# XO345-1B.net
KiCad netlist of a schematic drawn in EAGLE
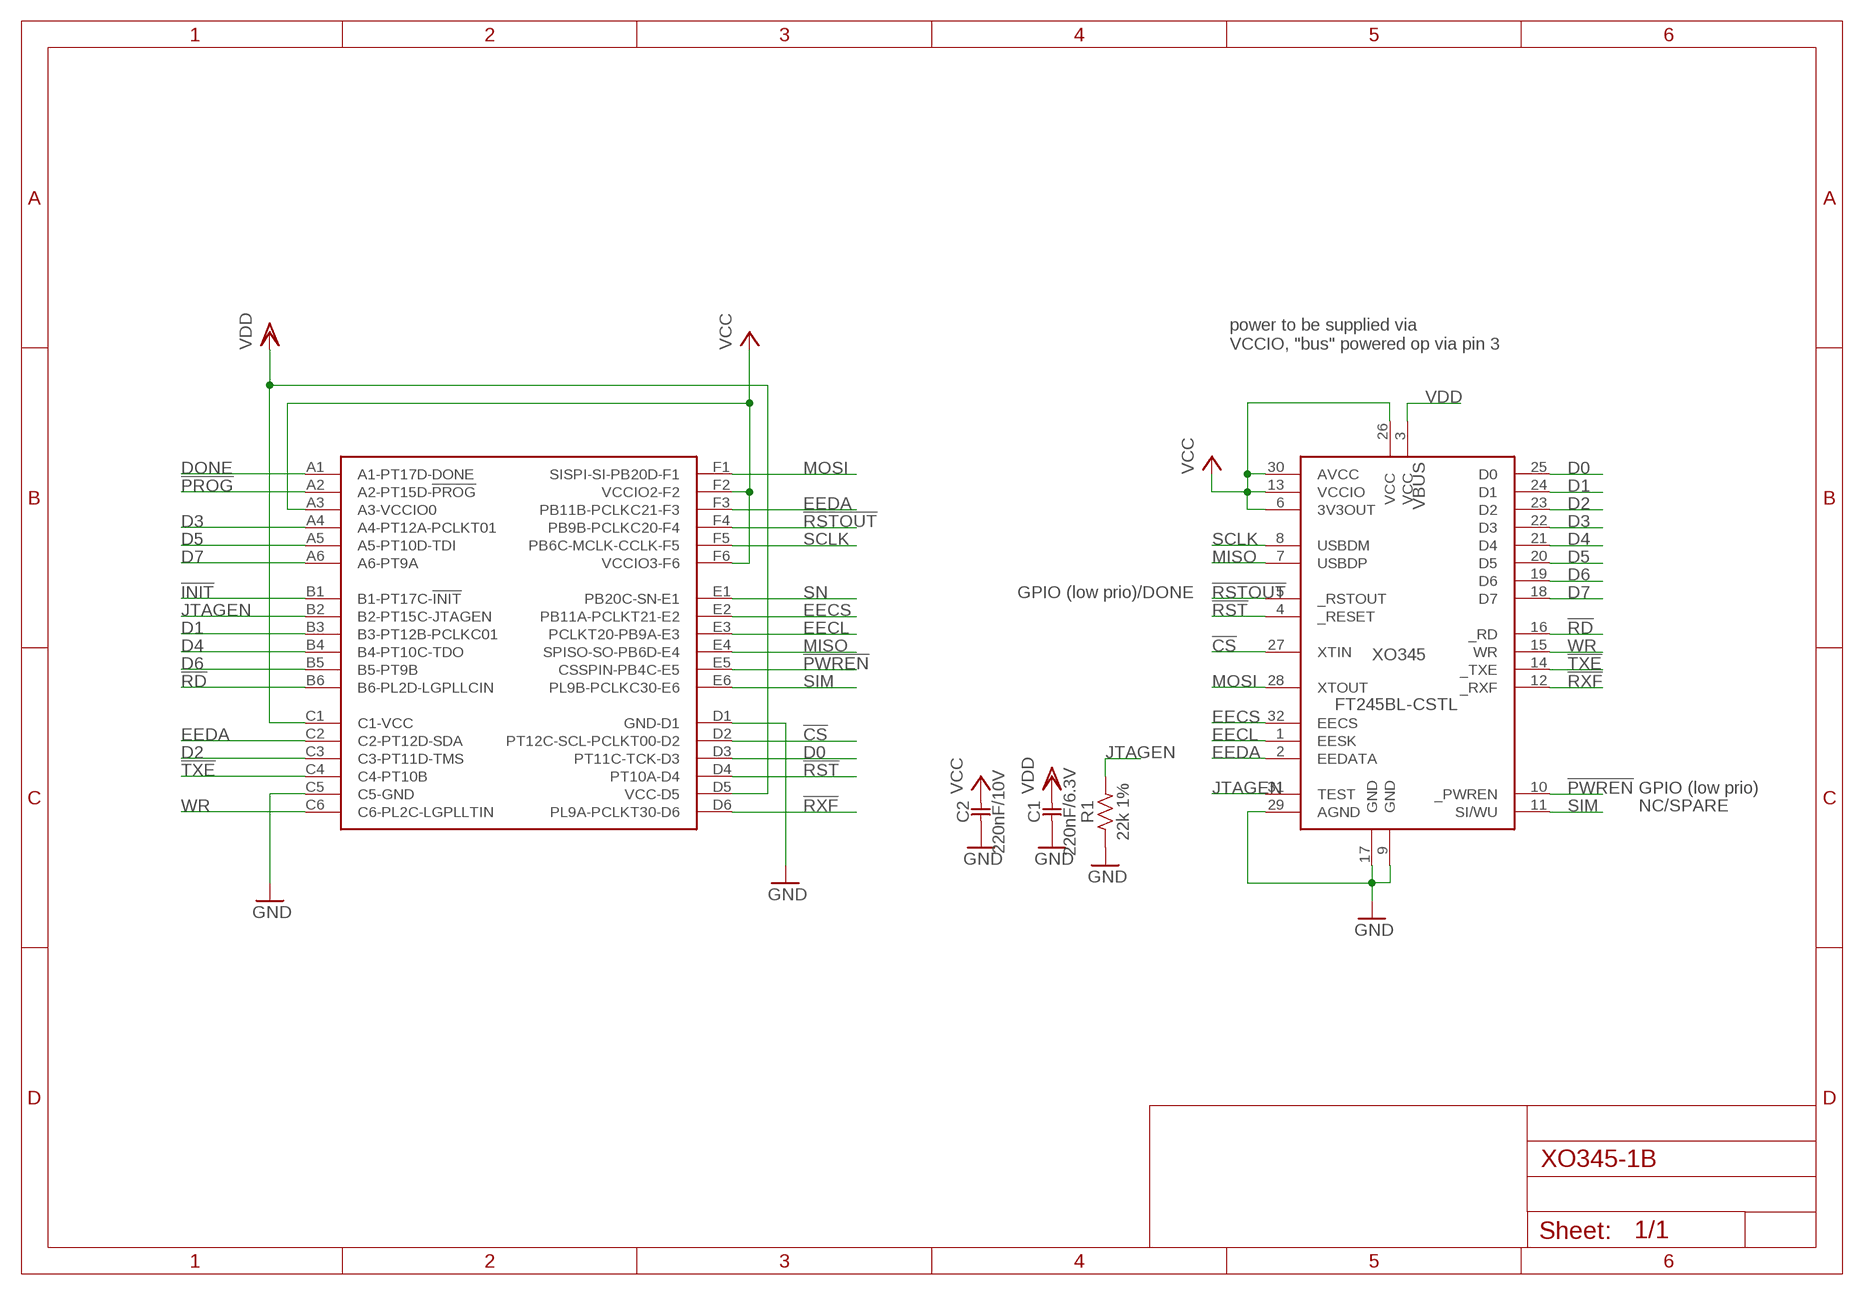
[diagram p0: schematic, sheet 1]

(export (version "E")
  (design (tool "Eeschema 10.0.6"))
  (components
    (comp (ref "C1")
      (value "220nF/6.3V")
      (footprint "eagle-import:C0402")
      (fields (field (name "MF") "TDK") (field (name "MFG_PARTNO") "C1005X5R1A224M050BC"))
      (libsource (lib "eagle-import") (part "CAP_0402"))
    )
    (comp (ref "C2")
      (value "220nF/10V")
      (footprint "eagle-import:C0603")
      (libsource (lib "eagle-import") (part "CAP_0603"))
    )
    (comp (ref "IC")
      (value "XO3-LCSP36")
      (footprint "eagle-import:WLCSP36")
      (fields
        (field (name "MF") "Lattice Semiconductor")
        (field (name "MFG_PARTNO") "LCMXO3L-1300E-5UWG36CTR50")
      )
      (libsource (lib "eagle-import") (part "XO3-LCSP36"))
    )
    (comp (ref "R1")
      (value "22k 1%")
      (footprint "eagle-import:R0402")
      (fields (field (name "MF") "Vishay") (field (name "MFG_PARTNO") "CRCW04022K70FKED"))
      (libsource (lib "eagle-import") (part "RES_0402"))
    )
    (comp (ref "XO345")
      (value "FT245BL-CSTL")
      (footprint "eagle-import:LQFP-32-CAST")
      (libsource (lib "eagle-import") (part "FT245BL-CSTL"))
    )
  )
  (nets
    (net (code "1") (name "/D0") (class "Default")
      (node (ref "IC") (pin "D3") (pinfunction "PT11C-TCK-D3_D3") (pintype "bidirectional"))
      (node (ref "XO345") (pin "25") (pinfunction "D0_25") (pintype "bidirectional"))
    )
    (net (code "2") (name "/D1") (class "Default")
      (node (ref "IC") (pin "B3") (pinfunction "B3-PT12B-PCLKC01_B3") (pintype "bidirectional"))
      (node (ref "XO345") (pin "24") (pinfunction "D1_24") (pintype "bidirectional"))
    )
    (net (code "3") (name "/D2") (class "Default")
      (node (ref "IC") (pin "C3") (pinfunction "C3-PT11D-TMS_C3") (pintype "bidirectional"))
      (node (ref "XO345") (pin "23") (pinfunction "D2_23") (pintype "bidirectional"))
    )
    (net (code "4") (name "/D3") (class "Default")
      (node (ref "IC") (pin "A4") (pinfunction "A4-PT12A-PCLKT01_A4") (pintype "bidirectional"))
      (node (ref "XO345") (pin "22") (pinfunction "D3_22") (pintype "bidirectional"))
    )
    (net (code "5") (name "/D4") (class "Default")
      (node (ref "IC") (pin "B4") (pinfunction "B4-PT10C-TDO_B4") (pintype "bidirectional"))
      (node (ref "XO345") (pin "21") (pinfunction "D4_21") (pintype "bidirectional"))
    )
    (net (code "6") (name "/D5") (class "Default")
      (node (ref "IC") (pin "A5") (pinfunction "A5-PT10D-TDI_A5") (pintype "bidirectional"))
      (node (ref "XO345") (pin "20") (pinfunction "D5_20") (pintype "bidirectional"))
    )
    (net (code "7") (name "/D6") (class "Default")
      (node (ref "IC") (pin "B5") (pinfunction "B5-PT9B_B5") (pintype "bidirectional"))
      (node (ref "XO345") (pin "19") (pinfunction "D6_19") (pintype "bidirectional"))
    )
    (net (code "8") (name "/D7") (class "Default")
      (node (ref "IC") (pin "A6") (pinfunction "A6-PT9A_A6") (pintype "bidirectional"))
      (node (ref "XO345") (pin "18") (pinfunction "D7_18") (pintype "bidirectional"))
    )
    (net (code "9") (name "/DONE") (class "Default")
      (node (ref "IC") (pin "A1") (pinfunction "A1-PT17D-DONE_A1") (pintype "bidirectional"))
    )
    (net (code "10") (name "/EECL") (class "Default")
      (node (ref "IC") (pin "E3") (pinfunction "PCLKT20-PB9A-E3_E3") (pintype "bidirectional"))
      (node (ref "XO345") (pin "1") (pinfunction "EESK_1") (pintype "output"))
    )
    (net (code "11") (name "/EECS") (class "Default")
      (node (ref "IC") (pin "E2") (pinfunction "PB11A-PCLKT21-E2_E2") (pintype "bidirectional"))
      (node (ref "XO345") (pin "32") (pinfunction "EECS_32") (pintype "bidirectional"))
    )
    (net (code "12") (name "/EEDA") (class "Default")
      (node (ref "IC") (pin "C2") (pinfunction "C2-PT12D-SDA_C2") (pintype "bidirectional"))
      (node (ref "IC") (pin "F3") (pinfunction "PB11B-PCLKC21-F3_F3") (pintype "bidirectional"))
      (node (ref "XO345") (pin "2") (pinfunction "EEDATA_2") (pintype "bidirectional"))
    )
    (net (code "13") (name "/JTAGEN") (class "Default")
      (node (ref "IC") (pin "B2") (pinfunction "B2-PT15C-JTAGEN_B2") (pintype "bidirectional"))
      (node (ref "R1") (pin "2") (pinfunction "2_2") (pintype "passive"))
      (node (ref "XO345") (pin "31") (pinfunction "TEST_31") (pintype "input"))
    )
    (net (code "14") (name "/MISO") (class "Default")
      (node (ref "IC") (pin "E4") (pinfunction "SPISO-SO-PB6D-E4_E4") (pintype "bidirectional"))
      (node (ref "XO345") (pin "7") (pinfunction "USBDP_7") (pintype "bidirectional"))
    )
    (net (code "15") (name "/MOSI") (class "Default")
      (node (ref "IC") (pin "F1") (pinfunction "SISPI-SI-PB20D-F1_F1") (pintype "bidirectional"))
      (node (ref "XO345") (pin "28") (pinfunction "XTOUT_28") (pintype "output"))
    )
    (net (code "16") (name "/SCLK") (class "Default")
      (node (ref "IC") (pin "F5") (pinfunction "PB6C-MCLK-CCLK-F5_F5") (pintype "bidirectional"))
      (node (ref "XO345") (pin "8") (pinfunction "USBDM_8") (pintype "bidirectional"))
    )
    (net (code "17") (name "/SIM") (class "Default")
      (node (ref "IC") (pin "E6") (pinfunction "PL9B-PCLKC30-E6_E6") (pintype "bidirectional"))
      (node (ref "XO345") (pin "11") (pinfunction "SI/WU_11") (pintype "input"))
    )
    (net (code "18") (name "/SN") (class "Default")
      (node (ref "IC") (pin "E1") (pinfunction "PB20C-SN-E1_E1") (pintype "bidirectional"))
    )
    (net (code "19") (name "/WR") (class "Default")
      (node (ref "IC") (pin "C6") (pinfunction "C6-PL2C-LGPLLTIN_C6") (pintype "bidirectional"))
      (node (ref "XO345") (pin "15") (pinfunction "WR_15") (pintype "input"))
    )
    (net (code "20") (name "/~{CS}") (class "Default")
      (node (ref "IC") (pin "D2") (pinfunction "PT12C-SCL-PCLKT00-D2_D2") (pintype "bidirectional"))
      (node (ref "XO345") (pin "27") (pinfunction "XTIN_27") (pintype "input"))
    )
    (net (code "21") (name "/~{INIT}") (class "Default")
      (node (ref "IC") (pin "B1") (pinfunction "B1-PT17C-~{INIT}_B1") (pintype "bidirectional"))
    )
    (net (code "22") (name "/~{PROG}") (class "Default")
      (node (ref "IC") (pin "A2") (pinfunction "A2-PT15D-~{PROG}_A2") (pintype "bidirectional"))
    )
    (net (code "23") (name "/~{PWREN}") (class "Default")
      (node (ref "IC") (pin "E5") (pinfunction "CSSPIN-PB4C-E5_E5") (pintype "bidirectional"))
      (node (ref "XO345") (pin "10") (pinfunction "_PWREN_10") (pintype "output"))
    )
    (net (code "24") (name "/~{RD}") (class "Default")
      (node (ref "IC") (pin "B6") (pinfunction "B6-PL2D-LGPLLCIN_B6") (pintype "bidirectional"))
      (node (ref "XO345") (pin "16") (pinfunction "_RD_16") (pintype "input"))
    )
    (net (code "25") (name "/~{RSTOUT}") (class "Default")
      (node (ref "IC") (pin "F4") (pinfunction "PB9B-PCLKC20-F4_F4") (pintype "bidirectional"))
      (node (ref "XO345") (pin "5") (pinfunction "_RSTOUT_5") (pintype "output"))
    )
    (net (code "26") (name "/~{RST}") (class "Default")
      (node (ref "IC") (pin "D4") (pinfunction "PT10A-D4_D4") (pintype "bidirectional"))
      (node (ref "XO345") (pin "4") (pinfunction "_RESET_4") (pintype "input"))
    )
    (net (code "27") (name "/~{RXF}") (class "Default")
      (node (ref "IC") (pin "D6") (pinfunction "PL9A-PCLKT30-D6_D6") (pintype "bidirectional"))
      (node (ref "XO345") (pin "12") (pinfunction "_RXF_12") (pintype "output"))
    )
    (net (code "28") (name "/~{TXE}") (class "Default")
      (node (ref "IC") (pin "C4") (pinfunction "C4-PT10B_C4") (pintype "bidirectional"))
      (node (ref "XO345") (pin "14") (pinfunction "_TXE_14") (pintype "output"))
    )
    (net (code "29") (name "GND") (class "Default")
      (node (ref "C1") (pin "1") (pinfunction "1_1") (pintype "passive"))
      (node (ref "C2") (pin "1") (pinfunction "1_1") (pintype "passive"))
      (node (ref "IC") (pin "C5") (pinfunction "C5-GND_C5") (pintype "bidirectional"))
      (node (ref "IC") (pin "D1") (pinfunction "GND-D1_D1") (pintype "bidirectional"))
      (node (ref "R1") (pin "1") (pinfunction "1_1") (pintype "passive"))
      (node (ref "XO345") (pin "17") (pinfunction "GND_17") (pintype "power_in"))
      (node (ref "XO345") (pin "29") (pinfunction "AGND_29") (pintype "power_in"))
      (node (ref "XO345") (pin "9") (pinfunction "GND_9") (pintype "power_in"))
    )
    (net (code "30") (name "VCC") (class "Default")
      (node (ref "C2") (pin "2") (pinfunction "2_2") (pintype "passive"))
      (node (ref "IC") (pin "A3") (pinfunction "A3-VCCIO0_A3") (pintype "bidirectional"))
      (node (ref "IC") (pin "F2") (pinfunction "VCCIO2-F2_F2") (pintype "bidirectional"))
      (node (ref "IC") (pin "F6") (pinfunction "VCCIO3-F6_F6") (pintype "bidirectional"))
      (node (ref "XO345") (pin "13") (pinfunction "VCCIO_13") (pintype "power_in"))
      (node (ref "XO345") (pin "26") (pinfunction "VCC_26") (pintype "power_in"))
      (node (ref "XO345") (pin "30") (pinfunction "AVCC_30") (pintype "power_in"))
      (node (ref "XO345") (pin "6") (pinfunction "3V3OUT_6") (pintype "output"))
    )
    (net (code "31") (name "VDD") (class "Default")
      (node (ref "C1") (pin "2") (pinfunction "2_2") (pintype "passive"))
      (node (ref "IC") (pin "C1") (pinfunction "C1-VCC_C1") (pintype "bidirectional"))
      (node (ref "IC") (pin "D5") (pinfunction "VCC-D5_D5") (pintype "bidirectional"))
      (node (ref "XO345") (pin "3") (pinfunction "VCC_3") (pintype "power_in"))
    )
  )
)
